# midi.net
KiCad netlist of a schematic drawn in EAGLE
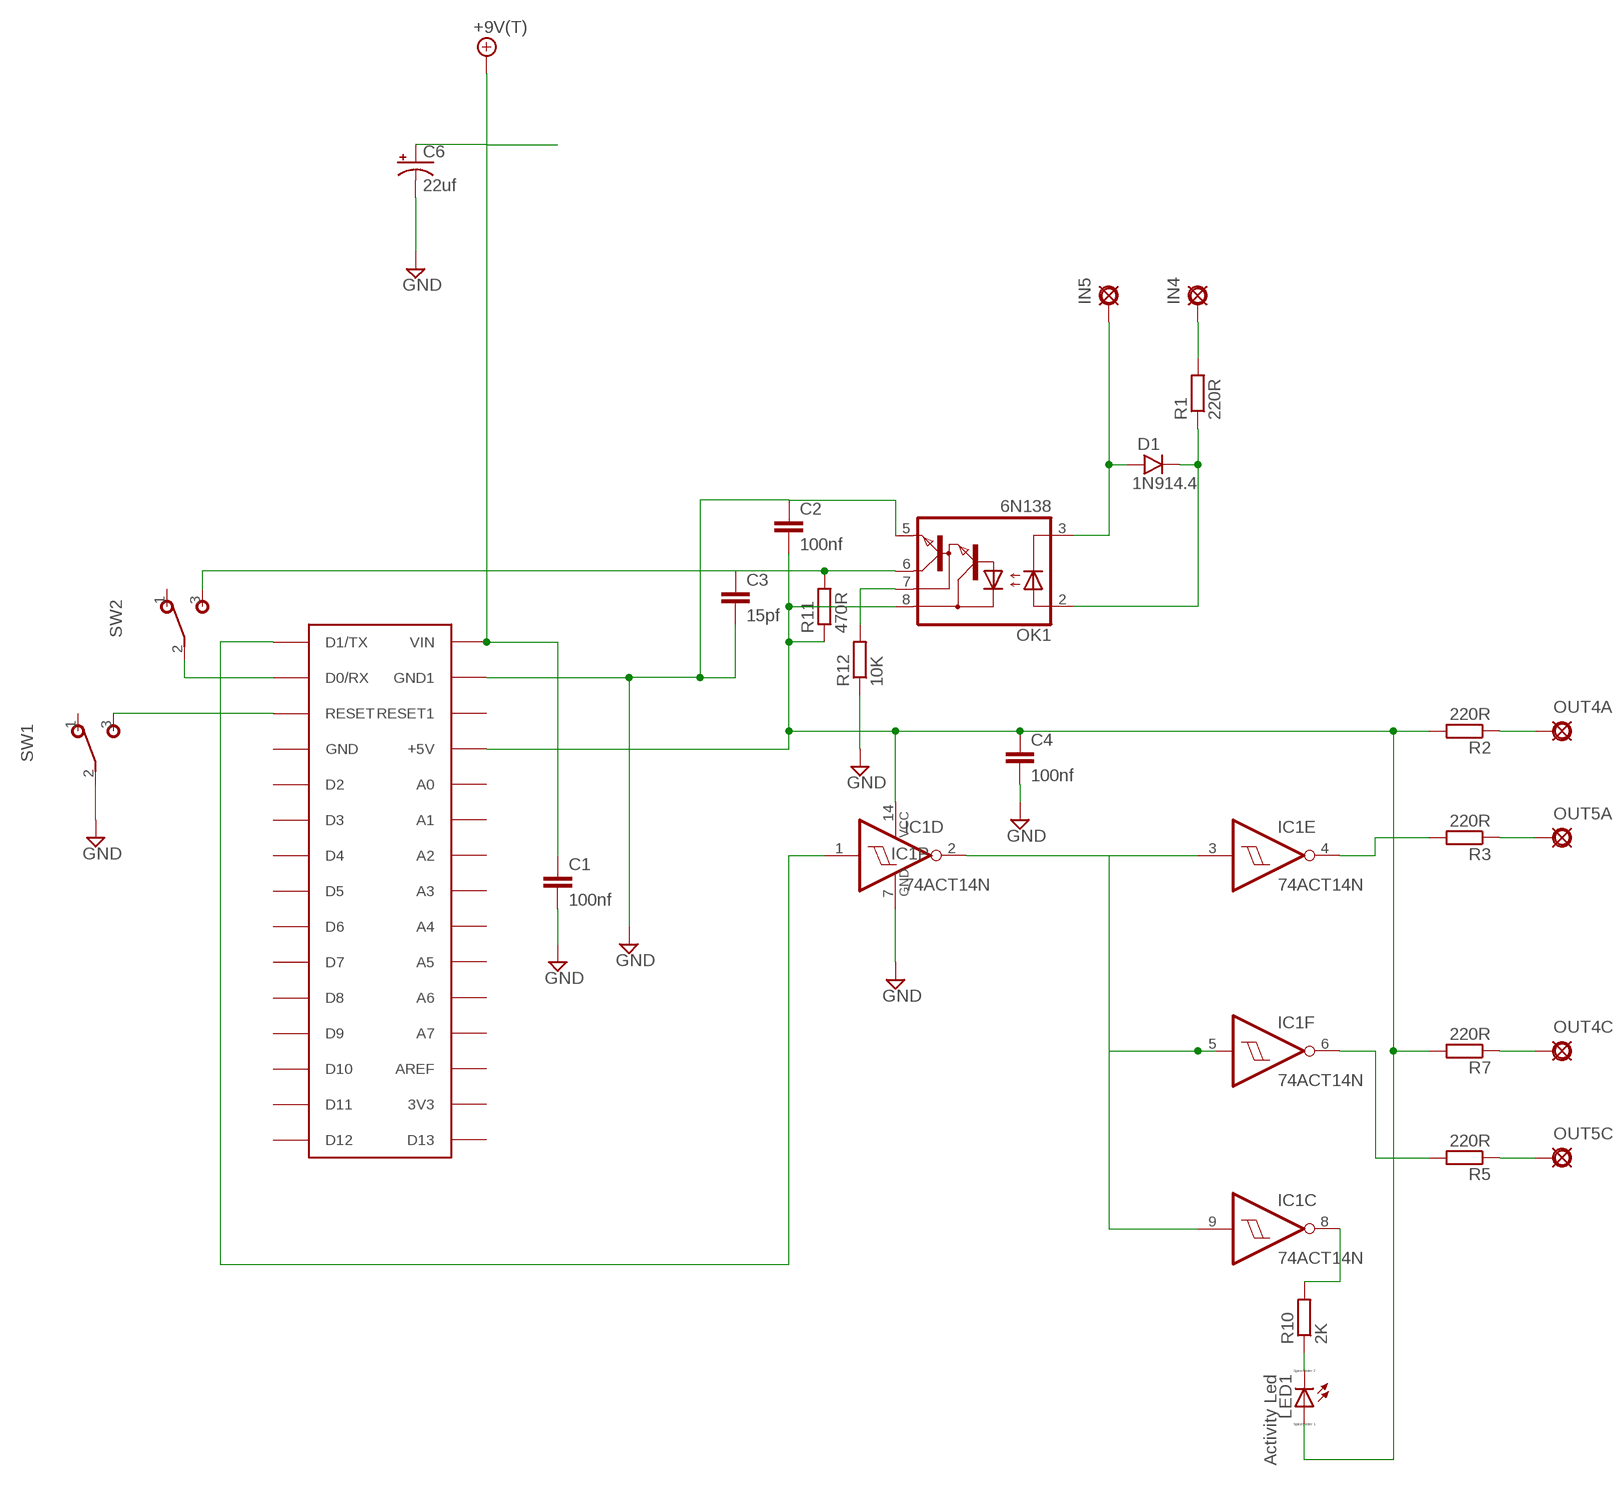
[diagram p0: schematic, sheet 1]

(export (version "E")
  (design (tool "Eeschema 10.0.6"))
  (components
    (comp (ref "+9V1")
      (value "+9V(T)")
      (footprint "eagle-import:SQUARE")
      (libsource (lib "eagle-import") (part "+9V(T)"))
    )
    (comp (ref "C1")
      (value "100nf")
      (footprint "eagle-import:C5B2.5")
      (libsource (lib "eagle-import") (part "C5/2.5"))
    )
    (comp (ref "C2")
      (value "100nf")
      (footprint "eagle-import:C5B2.5")
      (libsource (lib "eagle-import") (part "C5/2.5"))
    )
    (comp (ref "C3")
      (value "15pf")
      (footprint "eagle-import:050X030_025")
      (libsource (lib "eagle-import") (part "050X030_0251"))
    )
    (comp (ref "C4")
      (value "100nf")
      (footprint "eagle-import:C5B2.5")
      (libsource (lib "eagle-import") (part "C5/2.5"))
    )
    (comp (ref "C6")
      (value "22uf")
      (footprint "eagle-import:050_020_1")
      (libsource (lib "eagle-import") (part "0501"))
    )
    (comp (ref "D1")
      (value "1N914.4")
      (footprint "eagle-import:DO35-4")
      (libsource (lib "eagle-import") (part "1N914.4"))
    )
    (comp (ref "IC1")
      (value "74ACT14N")
      (footprint "eagle-import:DIL14")
      (libsource (lib "eagle-import") (part "7414NACT"))
    )
    (comp (ref "IN4")
      (value "PAD8")
      (footprint "eagle-import:OCTOGON")
      (libsource (lib "eagle-import") (part "PAD8"))
    )
    (comp (ref "IN5")
      (value "PAD8")
      (footprint "eagle-import:OCTOGON")
      (libsource (lib "eagle-import") (part "PAD8"))
    )
    (comp (ref "LED1")
      (value "Activity Led")
      (footprint "eagle-import:LED_1206")
      (libsource (lib "eagle-import") (part "LED_E"))
    )
    (comp (ref "OK1")
      (value "6N138")
      (footprint "eagle-import:DIL08")
      (fields (field (name "MF") "VISHAY/TELEFUNKEN"))
      (libsource (lib "eagle-import") (part "6N138"))
    )
    (comp (ref "OUT4A")
      (value "PAD8")
      (footprint "eagle-import:OCTOGON")
      (libsource (lib "eagle-import") (part "PAD8"))
    )
    (comp (ref "OUT4C")
      (value "PAD8")
      (footprint "eagle-import:OCTOGON")
      (libsource (lib "eagle-import") (part "PAD8"))
    )
    (comp (ref "OUT5A")
      (value "PAD8")
      (footprint "eagle-import:OCTOGON")
      (libsource (lib "eagle-import") (part "PAD8"))
    )
    (comp (ref "OUT5C")
      (value "PAD8")
      (footprint "eagle-import:OCTOGON")
      (libsource (lib "eagle-import") (part "PAD8"))
    )
    (comp (ref "R1")
      (value "220R")
      (footprint "eagle-import:0204_7")
      (libsource (lib "eagle-import") (part "R-EU_0204/7"))
    )
    (comp (ref "R2")
      (value "220R")
      (footprint "eagle-import:0204_7")
      (libsource (lib "eagle-import") (part "R-EU_0204/7"))
    )
    (comp (ref "R3")
      (value "220R")
      (footprint "eagle-import:0204_7")
      (libsource (lib "eagle-import") (part "R-EU_0204/7"))
    )
    (comp (ref "R5")
      (value "220R")
      (footprint "eagle-import:0204_7")
      (libsource (lib "eagle-import") (part "R-EU_0204/7"))
    )
    (comp (ref "R7")
      (value "220R")
      (footprint "eagle-import:0204_7")
      (libsource (lib "eagle-import") (part "R-EU_0204/7"))
    )
    (comp (ref "R10")
      (value "2K")
      (footprint "eagle-import:0204_7")
      (libsource (lib "eagle-import") (part "R-EU_0204/7"))
    )
    (comp (ref "R11")
      (value "470R")
      (footprint "eagle-import:0204_7")
      (libsource (lib "eagle-import") (part "R-EU_0204/7"))
    )
    (comp (ref "R12")
      (value "10K")
      (footprint "eagle-import:0204_7")
      (libsource (lib "eagle-import") (part "R-EU_0204/7"))
    )
    (comp (ref "SW1")
      (value "SPDT")
      (footprint "eagle-import:M9040P")
      (libsource (lib "eagle-import") (part "SPDT"))
    )
    (comp (ref "SW2")
      (value "SPDT")
      (footprint "eagle-import:M9040P")
      (libsource (lib "eagle-import") (part "SPDT"))
    )
    (comp (ref "U$1")
      (value "ARDUINONANO")
      (footprint "eagle-import:PDIP-32")
      (libsource (lib "eagle-import") (part "ARDUINONANO"))
    )
  )
  (nets
    (net (code "1") (name "+9V(T)") (class "Default")
      (node (ref "+9V1") (pin "1") (pinfunction "+9V_1") (pintype "power_in"))
      (node (ref "C1") (pin "1") (pinfunction "1_1") (pintype "passive"))
      (node (ref "C6") (pin "+") (pinfunction "+_+") (pintype "passive"))
      (node (ref "U$1") (pin "VIN") (pinfunction "VIN_VIN") (pintype "bidirectional"))
    )
    (net (code "2") (name "GND") (class "Default")
      (node (ref "C1") (pin "2") (pinfunction "2_2") (pintype "passive"))
      (node (ref "C2") (pin "1") (pinfunction "1_1") (pintype "passive"))
      (node (ref "C3") (pin "2") (pinfunction "2_2") (pintype "passive"))
      (node (ref "C4") (pin "2") (pinfunction "2_2") (pintype "passive"))
      (node (ref "C6") (pin "-") (pinfunction "-_-") (pintype "passive"))
      (node (ref "IC1") (pin "7") (pinfunction "GND_7") (pintype "power_in"))
      (node (ref "OK1") (pin "5") (pinfunction "GND_5") (pintype "passive"))
      (node (ref "R12") (pin "1") (pinfunction "1_1") (pintype "passive"))
      (node (ref "SW1") (pin "2") (pinfunction "P_2") (pintype "passive"))
      (node (ref "U$1") (pin "GND1") (pinfunction "GND1_GND1") (pintype "bidirectional"))
    )
    (net (code "3") (name "Net-(IC1C-I)") (class "Default")
      (node (ref "IC1") (pin "2") (pinfunction "O_2") (pintype "output"))
      (node (ref "IC1") (pin "3") (pinfunction "I_3") (pintype "input"))
      (node (ref "IC1") (pin "5") (pinfunction "I_5") (pintype "input"))
      (node (ref "IC1") (pin "9") (pinfunction "I_9") (pintype "input"))
    )
    (net (code "4") (name "Net-(IC1C-O)") (class "Default")
      (node (ref "IC1") (pin "8") (pinfunction "O_8") (pintype "output"))
      (node (ref "R10") (pin "2") (pinfunction "2_2") (pintype "passive"))
    )
    (net (code "5") (name "Net-(IC1D-I)") (class "Default")
      (node (ref "IC1") (pin "1") (pinfunction "I_1") (pintype "input"))
      (node (ref "U$1") (pin "D1/TX") (pinfunction "D1/TX_D1/TX") (pintype "bidirectional"))
    )
    (net (code "6") (name "Net-(IC1E-O)") (class "Default")
      (node (ref "IC1") (pin "4") (pinfunction "O_4") (pintype "output"))
      (node (ref "R3") (pin "2") (pinfunction "2_2") (pintype "passive"))
    )
    (net (code "7") (name "Net-(IC1F-O)") (class "Default")
      (node (ref "IC1") (pin "6") (pinfunction "O_6") (pintype "output"))
      (node (ref "R5") (pin "2") (pinfunction "2_2") (pintype "passive"))
    )
    (net (code "8") (name "Net-(IC1G-VCC)") (class "Default")
      (node (ref "C2") (pin "2") (pinfunction "2_2") (pintype "passive"))
      (node (ref "C4") (pin "1") (pinfunction "1_1") (pintype "passive"))
      (node (ref "IC1") (pin "14") (pinfunction "VCC_14") (pintype "power_in"))
      (node (ref "LED1") (pin "A") (pinfunction "A_A") (pintype "passive"))
      (node (ref "OK1") (pin "8") (pinfunction "VCC_8") (pintype "passive"))
      (node (ref "R11") (pin "1") (pinfunction "1_1") (pintype "passive"))
      (node (ref "R2") (pin "2") (pinfunction "2_2") (pintype "passive"))
      (node (ref "R7") (pin "2") (pinfunction "2_2") (pintype "passive"))
      (node (ref "U$1") (pin "+5V") (pinfunction "+5V_+5V") (pintype "bidirectional"))
    )
    (net (code "9") (name "Net-(IN4-PAD)") (class "Default")
      (node (ref "IN4") (pin "1") (pinfunction "PAD_1") (pintype "passive"))
      (node (ref "R1") (pin "2") (pinfunction "2_2") (pintype "passive"))
    )
    (net (code "10") (name "Net-(IN5-PAD)") (class "Default")
      (node (ref "D1") (pin "A") (pinfunction "A_A") (pintype "passive"))
      (node (ref "IN5") (pin "1") (pinfunction "PAD_1") (pintype "passive"))
      (node (ref "OK1") (pin "3") (pinfunction "C_3") (pintype "passive"))
    )
    (net (code "11") (name "Net-(LED1-PadC)") (class "Default")
      (node (ref "LED1") (pin "C") (pinfunction "C_C") (pintype "passive"))
      (node (ref "R10") (pin "1") (pinfunction "1_1") (pintype "passive"))
    )
    (net (code "12") (name "Net-(OK1-A)") (class "Default")
      (node (ref "D1") (pin "C") (pinfunction "C_C") (pintype "passive"))
      (node (ref "OK1") (pin "2") (pinfunction "A_2") (pintype "passive"))
      (node (ref "R1") (pin "1") (pinfunction "1_1") (pintype "passive"))
    )
    (net (code "13") (name "Net-(OK1-VB)") (class "Default")
      (node (ref "OK1") (pin "7") (pinfunction "VB_7") (pintype "passive"))
      (node (ref "R12") (pin "2") (pinfunction "2_2") (pintype "passive"))
    )
    (net (code "14") (name "Net-(OK1-VO)") (class "Default")
      (node (ref "C3") (pin "1") (pinfunction "1_1") (pintype "passive"))
      (node (ref "OK1") (pin "6") (pinfunction "VO_6") (pintype "passive"))
      (node (ref "R11") (pin "2") (pinfunction "2_2") (pintype "passive"))
      (node (ref "SW2") (pin "3") (pinfunction "S_3") (pintype "passive"))
    )
    (net (code "15") (name "Net-(OUT4A-PAD)") (class "Default")
      (node (ref "OUT4A") (pin "1") (pinfunction "PAD_1") (pintype "passive"))
      (node (ref "R2") (pin "1") (pinfunction "1_1") (pintype "passive"))
    )
    (net (code "16") (name "Net-(OUT4C-PAD)") (class "Default")
      (node (ref "OUT4C") (pin "1") (pinfunction "PAD_1") (pintype "passive"))
      (node (ref "R7") (pin "1") (pinfunction "1_1") (pintype "passive"))
    )
    (net (code "17") (name "Net-(OUT5A-PAD)") (class "Default")
      (node (ref "OUT5A") (pin "1") (pinfunction "PAD_1") (pintype "passive"))
      (node (ref "R3") (pin "1") (pinfunction "1_1") (pintype "passive"))
    )
    (net (code "18") (name "Net-(OUT5C-PAD)") (class "Default")
      (node (ref "OUT5C") (pin "1") (pinfunction "PAD_1") (pintype "passive"))
      (node (ref "R5") (pin "1") (pinfunction "1_1") (pintype "passive"))
    )
    (net (code "19") (name "Net-(SW1-S)") (class "Default")
      (node (ref "SW1") (pin "3") (pinfunction "S_3") (pintype "passive"))
      (node (ref "U$1") (pin "RESET") (pinfunction "RESET_RESET") (pintype "bidirectional"))
    )
    (net (code "20") (name "Net-(SW2-P)") (class "Default")
      (node (ref "SW2") (pin "2") (pinfunction "P_2") (pintype "passive"))
      (node (ref "U$1") (pin "D0/RX") (pinfunction "D0/RX_D0/RX") (pintype "bidirectional"))
    )
    (net (code "21") (name "unconnected-(SW1-O-Pad1)") (class "Default")
      (node (ref "SW1") (pin "1") (pinfunction "O_1") (pintype "passive"))
    )
    (net (code "22") (name "unconnected-(SW2-O-Pad1)") (class "Default")
      (node (ref "SW2") (pin "1") (pinfunction "O_1") (pintype "passive"))
    )
    (net (code "23") (name "unconnected-(U$1-Pad3V3)") (class "Default")
      (node (ref "U$1") (pin "3V3") (pinfunction "3V3_3V3") (pintype "bidirectional"))
    )
    (net (code "24") (name "unconnected-(U$1-PadA0)") (class "Default")
      (node (ref "U$1") (pin "A0") (pinfunction "A0_A0") (pintype "bidirectional"))
    )
    (net (code "25") (name "unconnected-(U$1-PadA1)") (class "Default")
      (node (ref "U$1") (pin "A1") (pinfunction "A1_A1") (pintype "bidirectional"))
    )
    (net (code "26") (name "unconnected-(U$1-PadA2)") (class "Default")
      (node (ref "U$1") (pin "A2") (pinfunction "A2_A2") (pintype "bidirectional"))
    )
    (net (code "27") (name "unconnected-(U$1-PadA3)") (class "Default")
      (node (ref "U$1") (pin "A3") (pinfunction "A3_A3") (pintype "bidirectional"))
    )
    (net (code "28") (name "unconnected-(U$1-PadA4)") (class "Default")
      (node (ref "U$1") (pin "A4") (pinfunction "A4_A4") (pintype "bidirectional"))
    )
    (net (code "29") (name "unconnected-(U$1-PadA5)") (class "Default")
      (node (ref "U$1") (pin "A5") (pinfunction "A5_A5") (pintype "bidirectional"))
    )
    (net (code "30") (name "unconnected-(U$1-PadA6)") (class "Default")
      (node (ref "U$1") (pin "A6") (pinfunction "A6_A6") (pintype "bidirectional"))
    )
    (net (code "31") (name "unconnected-(U$1-PadA7)") (class "Default")
      (node (ref "U$1") (pin "A7") (pinfunction "A7_A7") (pintype "bidirectional"))
    )
    (net (code "32") (name "unconnected-(U$1-PadAREF)") (class "Default")
      (node (ref "U$1") (pin "AREF") (pinfunction "AREF_AREF") (pintype "bidirectional"))
    )
    (net (code "33") (name "unconnected-(U$1-PadD2)") (class "Default")
      (node (ref "U$1") (pin "D2") (pinfunction "D2_D2") (pintype "bidirectional"))
    )
    (net (code "34") (name "unconnected-(U$1-PadD3)") (class "Default")
      (node (ref "U$1") (pin "D3") (pinfunction "D3_D3") (pintype "bidirectional"))
    )
    (net (code "35") (name "unconnected-(U$1-PadD4)") (class "Default")
      (node (ref "U$1") (pin "D4") (pinfunction "D4_D4") (pintype "bidirectional"))
    )
    (net (code "36") (name "unconnected-(U$1-PadD5)") (class "Default")
      (node (ref "U$1") (pin "D5") (pinfunction "D5_D5") (pintype "bidirectional"))
    )
    (net (code "37") (name "unconnected-(U$1-PadD6)") (class "Default")
      (node (ref "U$1") (pin "D6") (pinfunction "D6_D6") (pintype "bidirectional"))
    )
    (net (code "38") (name "unconnected-(U$1-PadD7)") (class "Default")
      (node (ref "U$1") (pin "D7") (pinfunction "D7_D7") (pintype "bidirectional"))
    )
    (net (code "39") (name "unconnected-(U$1-PadD8)") (class "Default")
      (node (ref "U$1") (pin "D8") (pinfunction "D8_D8") (pintype "bidirectional"))
    )
    (net (code "40") (name "unconnected-(U$1-PadD9)") (class "Default")
      (node (ref "U$1") (pin "D9") (pinfunction "D9_D9") (pintype "bidirectional"))
    )
    (net (code "41") (name "unconnected-(U$1-PadD10)") (class "Default")
      (node (ref "U$1") (pin "D10") (pinfunction "D10_D10") (pintype "bidirectional"))
    )
    (net (code "42") (name "unconnected-(U$1-PadD11)") (class "Default")
      (node (ref "U$1") (pin "D11") (pinfunction "D11_D11") (pintype "bidirectional"))
    )
    (net (code "43") (name "unconnected-(U$1-PadD12)") (class "Default")
      (node (ref "U$1") (pin "D12") (pinfunction "D12_D12") (pintype "bidirectional"))
    )
    (net (code "44") (name "unconnected-(U$1-PadD13)") (class "Default")
      (node (ref "U$1") (pin "D13") (pinfunction "D13_D13") (pintype "bidirectional"))
    )
    (net (code "45") (name "unconnected-(U$1-PadGND)") (class "Default")
      (node (ref "U$1") (pin "GND") (pinfunction "GND_GND") (pintype "bidirectional"))
    )
    (net (code "46") (name "unconnected-(U$1-PadRESET1)") (class "Default")
      (node (ref "U$1") (pin "RESET1") (pinfunction "RESET1_RESET1") (pintype "bidirectional"))
    )
  )
)
